# UART_bus.net
KiCad netlist of a schematic drawn in Altium Designer
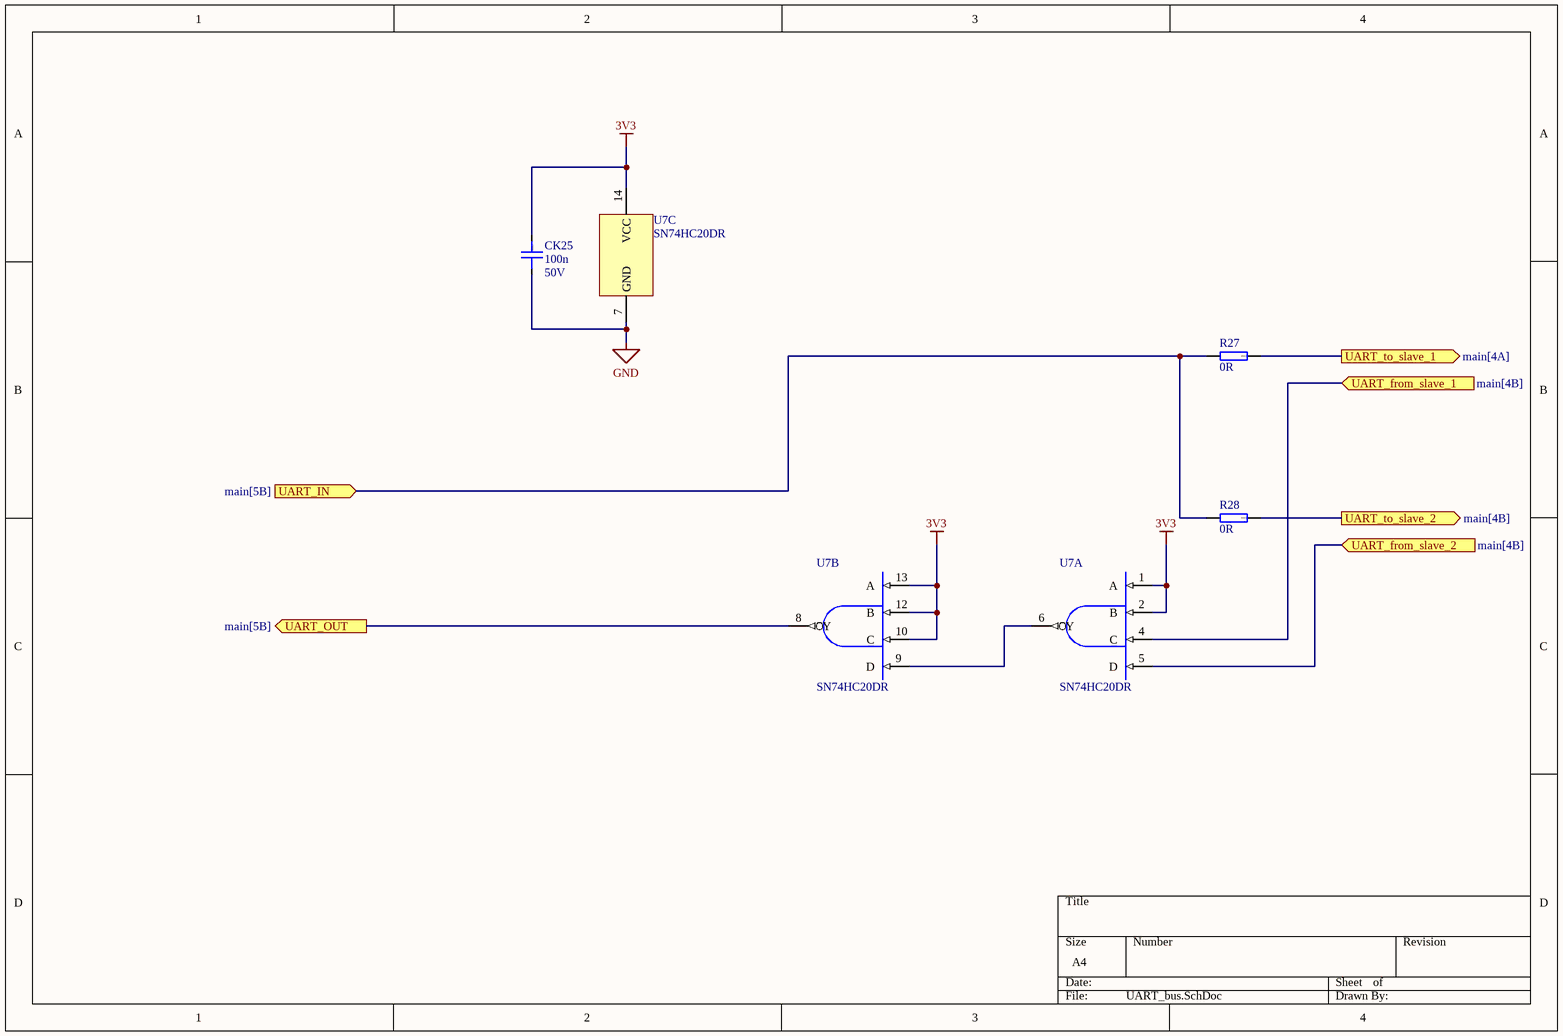
[diagram p0: UART_bus.SchDoc]

(export (version "E")
  (design (tool "Eeschema 10.0.6"))
  (components
    (comp (ref "CK25")
      (value "100n")
      (footprint "CAP0603")
      (description "50V 100nF X7R ±10% 0603 Multilayer Ceramic Capacitors MLCC - SMD/SMT ROHS")
      (fields (field (name "JLCPCB PART") "C14663") (field (name "VOLTAGE RATING") "50V"))
      (libsource (lib "Kubikova ultra knihovna") (part "Cap 100n 0603"))
    )
    (comp (ref "R27")
      (value "0R")
      (footprint "RESC2012X06N(SMR0805)")
      (description "125mW Thick Film Resistors 150V ±800ppm/℃ ±1% 0Ω 0805 Chip Resistor - Surface Mount ROHS")
      (fields (field (name "JLCPCB PART") "C17477") (field (name "AUTHOR") "JP/27.03.2014"))
      (libsource (lib "Kubikova ultra knihovna") (part "Res 0R 0805"))
    )
    (comp (ref "R28")
      (value "0R")
      (footprint "RESC2012X06N(SMR0805)")
      (description "125mW Thick Film Resistors 150V ±800ppm/℃ ±1% 0Ω 0805 Chip Resistor - Surface Mount ROHS")
      (fields (field (name "JLCPCB PART") "C17477") (field (name "AUTHOR") "JP/27.03.2014"))
      (libsource (lib "Kubikova ultra knihovna") (part "Res 0R 0805"))
    )
    (comp (ref "U7")
      (value "SN74HC20DR")
      (footprint "SOIC14")
      (description "2V~6V 2uA 2 19ns@6V,50pF NAND Gates SOIC-14 Logic Gates ROHS")
      (fields (field (name "JLCPCB PART") "C2867684"))
      (libsource (lib "") (part "SN74HC20DR_1"))
    )
  )
  (nets
    (net (code "1") (name "/UART_IN") (class "Default")
      (node (ref "R27") (pin "1") (pinfunction "1_1") (pintype "passive"))
      (node (ref "R28") (pin "1") (pinfunction "1_1") (pintype "passive"))
    )
    (net (code "2") (name "/UART_OUT") (class "Default")
      (node (ref "U7") (pin "8") (pinfunction "Y_8") (pintype "output"))
    )
    (net (code "3") (name "/UART_from_slave_1") (class "Default")
      (node (ref "U7") (pin "4") (pinfunction "C_4") (pintype "input"))
    )
    (net (code "4") (name "/UART_from_slave_2") (class "Default")
      (node (ref "U7") (pin "5") (pinfunction "D_5") (pintype "input"))
    )
    (net (code "5") (name "/UART_to_slave_1") (class "Default")
      (node (ref "R27") (pin "2") (pinfunction "2_2") (pintype "passive"))
    )
    (net (code "6") (name "/UART_to_slave_2") (class "Default")
      (node (ref "R28") (pin "2") (pinfunction "2_2") (pintype "passive"))
    )
    (net (code "7") (name "3V3") (class "Default")
      (node (ref "CK25") (pin "1") (pinfunction "1_1") (pintype "passive"))
      (node (ref "U7") (pin "1") (pinfunction "A_1") (pintype "input"))
      (node (ref "U7") (pin "10") (pinfunction "C_10") (pintype "input"))
      (node (ref "U7") (pin "12") (pinfunction "B_12") (pintype "input"))
      (node (ref "U7") (pin "13") (pinfunction "A_13") (pintype "input"))
      (node (ref "U7") (pin "14") (pinfunction "VCC_14") (pintype "passive"))
      (node (ref "U7") (pin "2") (pinfunction "B_2") (pintype "input"))
    )
    (net (code "8") (name "GND") (class "Default")
      (node (ref "CK25") (pin "2") (pinfunction "2_2") (pintype "passive"))
      (node (ref "U7") (pin "7") (pinfunction "GND_7") (pintype "passive"))
    )
    (net (code "9") (name "Net-(U7A-Y)") (class "Default")
      (node (ref "U7") (pin "6") (pinfunction "Y_6") (pintype "output"))
      (node (ref "U7") (pin "9") (pinfunction "D_9") (pintype "input"))
    )
  )
)
